# Controller.net
KiCad netlist of a schematic drawn in Altium Designer
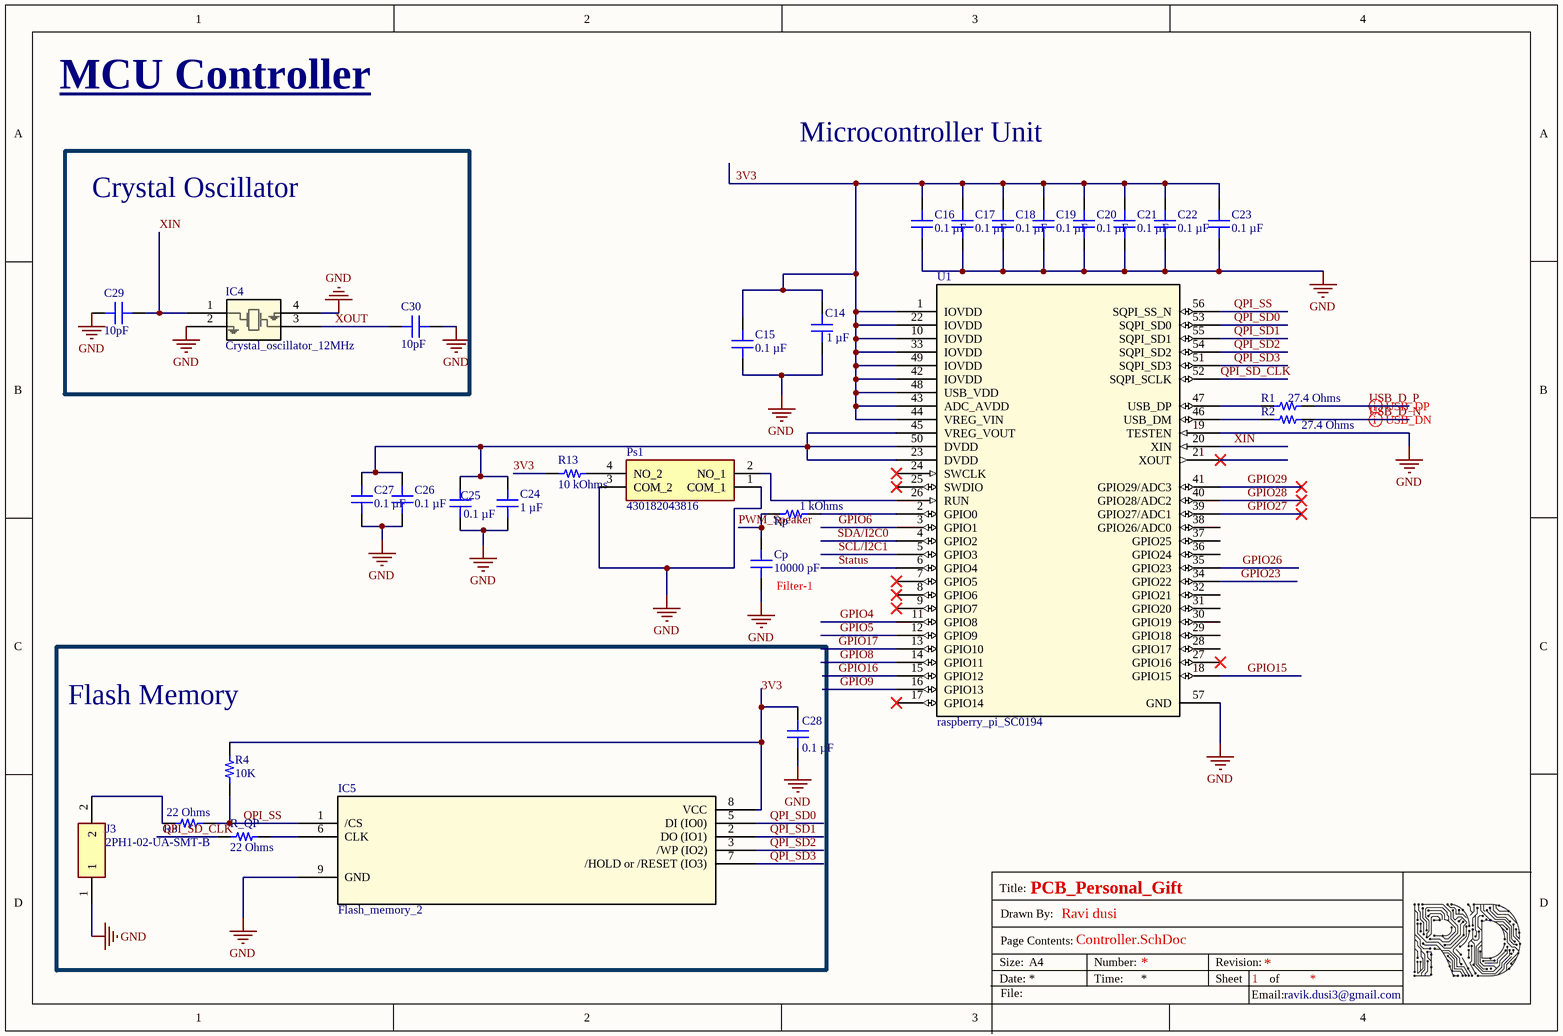
[diagram p0: Controller.SchDoc]

(export (version "E")
  (design (tool "Eeschema 10.0.6"))
  (components
    (comp (ref "C14")
      (value "1 µF")
      (footprint "CAP 0402_1005")
      (description "CAP CER 1UF 10V X7S 0402")
      (fields
        (field (name "PART NUMBER") "GRM155C71A105KE11D")
        (field (name "MANUFACTURER") "Murata Electronics")
      )
      (libsource (lib "Celestial Altium Library - altium_library") (part "Capacitor"))
    )
    (comp (ref "C15")
      (value "0.1 µF")
      (footprint "CAP 0402_1005")
      (description "CAP CER 0402 0.1UF 16V X7R 10%")
      (fields (field (name "PART NUMBER") "C0402C104K4RECAUTO") (field (name "MANUFACTURER") "KEMET"))
      (libsource (lib "Celestial Altium Library - altium_library") (part "Capacitor"))
    )
    (comp (ref "C16")
      (value "0.1 µF")
      (footprint "CAP 0402_1005")
      (description "CAP CER 0402 0.1UF 16V X7R 10%")
      (fields (field (name "PART NUMBER") "C0402C104K4RECAUTO") (field (name "MANUFACTURER") "KEMET"))
      (libsource (lib "Celestial Altium Library - altium_library") (part "Capacitor"))
    )
    (comp (ref "C17")
      (value "0.1 µF")
      (footprint "CAP 0402_1005")
      (description "CAP CER 0402 0.1UF 16V X7R 10%")
      (fields (field (name "PART NUMBER") "C0402C104K4RECAUTO") (field (name "MANUFACTURER") "KEMET"))
      (libsource (lib "Celestial Altium Library - altium_library") (part "Capacitor"))
    )
    (comp (ref "C18")
      (value "0.1 µF")
      (footprint "CAP 0402_1005")
      (description "CAP CER 0402 0.1UF 16V X7R 10%")
      (fields (field (name "PART NUMBER") "C0402C104K4RECAUTO") (field (name "MANUFACTURER") "KEMET"))
      (libsource (lib "Celestial Altium Library - altium_library") (part "Capacitor"))
    )
    (comp (ref "C19")
      (value "0.1 µF")
      (footprint "CAP 0402_1005")
      (description "CAP CER 0402 0.1UF 16V X7R 10%")
      (fields (field (name "PART NUMBER") "C0402C104K4RECAUTO") (field (name "MANUFACTURER") "KEMET"))
      (libsource (lib "Celestial Altium Library - altium_library") (part "Capacitor"))
    )
    (comp (ref "C20")
      (value "0.1 µF")
      (footprint "CAP 0402_1005")
      (description "CAP CER 0402 0.1UF 16V X7R 10%")
      (fields (field (name "PART NUMBER") "C0402C104K4RECAUTO") (field (name "MANUFACTURER") "KEMET"))
      (libsource (lib "Celestial Altium Library - altium_library") (part "Capacitor"))
    )
    (comp (ref "C21")
      (value "0.1 µF")
      (footprint "CAP 0402_1005")
      (description "CAP CER 0402 0.1UF 16V X7R 10%")
      (fields (field (name "PART NUMBER") "C0402C104K4RECAUTO") (field (name "MANUFACTURER") "KEMET"))
      (libsource (lib "Celestial Altium Library - altium_library") (part "Capacitor"))
    )
    (comp (ref "C22")
      (value "0.1 µF")
      (footprint "CAP 0402_1005")
      (description "CAP CER 0402 0.1UF 16V X7R 10%")
      (fields (field (name "PART NUMBER") "C0402C104K4RECAUTO") (field (name "MANUFACTURER") "KEMET"))
      (libsource (lib "Celestial Altium Library - altium_library") (part "Capacitor"))
    )
    (comp (ref "C23")
      (value "0.1 µF")
      (footprint "CAP 0402_1005")
      (description "CAP CER 0402 0.1UF 16V X7R 10%")
      (fields (field (name "PART NUMBER") "C0402C104K4RECAUTO") (field (name "MANUFACTURER") "KEMET"))
      (libsource (lib "Celestial Altium Library - altium_library") (part "Capacitor"))
    )
    (comp (ref "C24")
      (value "1 µF")
      (footprint "CAP 0402_1005")
      (description "CAP CER 1UF 10V X7S 0402")
      (fields
        (field (name "PART NUMBER") "GRM155C71A105KE11D")
        (field (name "MANUFACTURER") "Murata Electronics")
      )
      (libsource (lib "Celestial Altium Library - altium_library") (part "Capacitor"))
    )
    (comp (ref "C25")
      (value "0.1 µF")
      (footprint "CAP 0402_1005")
      (description "CAP CER 0402 0.1UF 16V X7R 10%")
      (fields (field (name "PART NUMBER") "C0402C104K4RECAUTO") (field (name "MANUFACTURER") "KEMET"))
      (libsource (lib "Celestial Altium Library - altium_library") (part "Capacitor"))
    )
    (comp (ref "C26")
      (value "0.1 µF")
      (footprint "CAP 0402_1005")
      (description "CAP CER 0402 0.1UF 16V X7R 10%")
      (fields (field (name "PART NUMBER") "C0402C104K4RECAUTO") (field (name "MANUFACTURER") "KEMET"))
      (libsource (lib "Celestial Altium Library - altium_library") (part "Capacitor"))
    )
    (comp (ref "C27")
      (value "0.1 µF")
      (footprint "CAP 0402_1005")
      (description "CAP CER 0402 0.1UF 16V X7R 10%")
      (fields (field (name "PART NUMBER") "C0402C104K4RECAUTO") (field (name "MANUFACTURER") "KEMET"))
      (libsource (lib "Celestial Altium Library - altium_library") (part "Capacitor"))
    )
    (comp (ref "C28")
      (value "0.1 µF")
      (footprint "CAP 0402_1005")
      (description "CAP CER 0402 0.1UF 16V X7R 10%")
      (fields (field (name "PART NUMBER") "C0402C104K4RECAUTO") (field (name "MANUFACTURER") "KEMET"))
      (libsource (lib "Celestial Altium Library - altium_library") (part "Capacitor"))
    )
    (comp (ref "C29")
      (value "10pF")
      (footprint "CAP 0402_1005")
      (description "CAP CER 10PF 50V C0G/NP0 0402")
      (fields (field (name "PART NUMBER") "04025U100JAT2A") (field (name "MANUFACTURER") "AVX Corporation"))
      (libsource (lib "Celestial Altium Library - altium_library") (part "Capacitor"))
    )
    (comp (ref "C30")
      (value "10pF")
      (footprint "CAP 0402_1005")
      (description "CAP CER 10PF 50V C0G/NP0 0402")
      (fields (field (name "PART NUMBER") "04025U100JAT2A") (field (name "MANUFACTURER") "AVX Corporation"))
      (libsource (lib "Celestial Altium Library - altium_library") (part "Capacitor"))
    )
    (comp (ref "Cp")
      (value "10000 pF")
      (footprint "CAP 0402_1005")
      (description "CAP CER 0402 10NF 50V X7R 20%")
      (fields
        (field (name "PART NUMBER") "C0402C103M5RECAUTO")
        (field (name "CAPACITANCE") "10000 pF")
        (field (name "MANUFACTURER") "KEMET")
      )
      (libsource (lib "Celestial Altium Library - altium_library (1)") (part "Capacitor"))
    )
    (comp (ref "IC4")
      (value "Crystal_oscillator_12MHz")
      (footprint "ABM8-272-T3_ABR")
      (libsource (lib "Personal_proj_lib") (part "Crystal_oscillator_12MHz"))
    )
    (comp (ref "IC5")
      (value "Flash_memory_2")
      (footprint "SON127P610X510X80-8N430X340")
      (description "FLASH - NOR Memory IC 128Mb (16M x 8) SPI - Quad I/O, QPI, DTR 133 MHz 8-SOIC")
      (libsource (lib "Personal_proj_lib") (part "Flash_memory_2"))
    )
    (comp (ref "J3")
      (value "2PH1-02-UA-SMT-B")
      (footprint "SamacSys:2PH102UASMTB")
      (description "Connector")
      (fields (field (name "MOUSER PART NUMBER") "737-2PH1-02-UA-SMT-B"))
      (libsource (lib "*") (part "2PH1-02-UA-SMT-B"))
    )
    (comp (ref "Ps1")
      (value "430182043816")
      (footprint "SamacSys:430182043816")
      (description "Switch")
      (fields (field (name "MOUSER PART NUMBER") "710-430182043816"))
      (libsource (lib "*") (part "430182043816"))
    )
    (comp (ref "R1")
      (value "27.4 Ohms")
      (footprint "RES 0402_1005")
      (description "RES 27.4 OHM 1% 1/16W 0402")
      (fields (field (name "PART NUMBER") "RC0402FR-0727R4L") (field (name "MANUFACTURER") "Yageo"))
      (libsource (lib "Celestial Altium Library - altium_library") (part "Resistor"))
    )
    (comp (ref "R2")
      (value "27.4 Ohms")
      (footprint "RES 0402_1005")
      (description "RES 27.4 OHM 1% 1/16W 0402")
      (fields (field (name "PART NUMBER") "RC0402FR-0727R4L") (field (name "MANUFACTURER") "Yageo"))
      (libsource (lib "Celestial Altium Library - altium_library") (part "Resistor"))
    )
    (comp (ref "R3")
      (value "22 Ohms")
      (footprint "RES 0402_1005")
      (description "RES SMD 22 OHM 0.5% 1/16W 0402")
      (fields (field (name "PART NUMBER") "RR0510R-220-D") (field (name "MANUFACTURER") "Susumu"))
      (libsource (lib "Celestial Altium Library - altium_library (1)") (part "Resistor"))
    )
    (comp (ref "R4")
      (value "10K")
      (footprint "RES 0402_1005")
      (description "RES 10K OHM 0.1% 1/10W 0402")
      (fields
        (field (name "PART NUMBER") "RP73PF1E10KBTD")
        (field (name "MANUFACTURER") "TE Connectivity Passive Product")
      )
      (libsource (lib "Celestial Altium Library - altium_library") (part "Resistor"))
    )
    (comp (ref "R13")
      (value "10 kOhms")
      (footprint "RES 0402_1005")
      (description "RES 10K OHM 0.1% 1/10W 0402")
      (fields
        (field (name "PART NUMBER") "RP73PF1E10KBTD")
        (field (name "MANUFACTURER") "TE Connectivity Passive Product")
      )
      (libsource (lib "Celestial Altium Library - altium_library") (part "Resistor"))
    )
    (comp (ref "Rp")
      (value "1 kOhms")
      (footprint "YAGEO RES 0402_1005")
      (description "RES SMD 1K OHM 0.1% 1/16W 0402")
      (fields (field (name "PART NUMBER") "AT0402BRD071KL") (field (name "MANUFACTURER") "Yageo"))
      (libsource (lib "Celestial Altium Library - altium_library (1)") (part "Resistor"))
    )
    (comp (ref "R_QP")
      (value "22 Ohms")
      (footprint "RES 0402_1005")
      (description "RES SMD 22 OHM 0.5% 1/16W 0402")
      (fields (field (name "PART NUMBER") "RR0510R-220-D") (field (name "MANUFACTURER") "Susumu"))
      (libsource (lib "Celestial Altium Library - altium_library (1)") (part "Resistor"))
    )
    (comp (ref "U1")
      (value "raspberry_pi_SC0194")
      (footprint "QFN56_7X7_RPI")
      (description "rp2040 rapberri Pi Microcontroller")
      (libsource (lib "Personal_proj_lib") (part "raspberry_pi_SC0194"))
    )
  )
  (nets
    (net (code "1") (name "/3V3") (class "Default")
      (node (ref "C14") (pin "2") (pinfunction "2_2") (pintype "passive"))
      (node (ref "C15") (pin "2") (pinfunction "2_2") (pintype "passive"))
      (node (ref "C16") (pin "2") (pinfunction "2_2") (pintype "passive"))
      (node (ref "C17") (pin "2") (pinfunction "2_2") (pintype "passive"))
      (node (ref "C18") (pin "2") (pinfunction "2_2") (pintype "passive"))
      (node (ref "C19") (pin "2") (pinfunction "2_2") (pintype "passive"))
      (node (ref "C20") (pin "2") (pinfunction "2_2") (pintype "passive"))
      (node (ref "C21") (pin "2") (pinfunction "2_2") (pintype "passive"))
      (node (ref "C22") (pin "2") (pinfunction "2_2") (pintype "passive"))
      (node (ref "C23") (pin "2") (pinfunction "2_2") (pintype "passive"))
      (node (ref "C28") (pin "2") (pinfunction "2_2") (pintype "passive"))
      (node (ref "IC5") (pin "8") (pinfunction "VCC_8") (pintype "power_in"))
      (node (ref "R13") (pin "1") (pinfunction "1_1") (pintype "passive"))
      (node (ref "R4") (pin "2") (pinfunction "2_2") (pintype "passive"))
      (node (ref "U1") (pin "1") (pinfunction "IOVDD_1") (pintype "power_in"))
      (node (ref "U1") (pin "10") (pinfunction "IOVDD_10") (pintype "power_in"))
      (node (ref "U1") (pin "22") (pinfunction "IOVDD_22") (pintype "power_in"))
      (node (ref "U1") (pin "33") (pinfunction "IOVDD_33") (pintype "power_in"))
      (node (ref "U1") (pin "42") (pinfunction "IOVDD_42") (pintype "power_in"))
      (node (ref "U1") (pin "43") (pinfunction "ADC_AVDD_43") (pintype "power_in"))
      (node (ref "U1") (pin "44") (pinfunction "VREG_VIN_44") (pintype "power_in"))
      (node (ref "U1") (pin "48") (pinfunction "USB_VDD_48") (pintype "power_in"))
      (node (ref "U1") (pin "49") (pinfunction "IOVDD_49") (pintype "power_in"))
    )
    (net (code "2") (name "/GPIO4") (class "Default")
      (node (ref "U1") (pin "11") (pinfunction "GPIO8_11") (pintype "bidirectional"))
    )
    (net (code "3") (name "/GPIO5") (class "Default")
      (node (ref "U1") (pin "12") (pinfunction "GPIO9_12") (pintype "bidirectional"))
    )
    (net (code "4") (name "/GPIO6") (class "Default")
      (node (ref "U1") (pin "3") (pinfunction "GPIO1_3") (pintype "bidirectional"))
    )
    (net (code "5") (name "/GPIO8") (class "Default")
      (node (ref "U1") (pin "14") (pinfunction "GPIO11_14") (pintype "bidirectional"))
    )
    (net (code "6") (name "/GPIO9") (class "Default")
      (node (ref "U1") (pin "16") (pinfunction "GPIO13_16") (pintype "bidirectional"))
    )
    (net (code "7") (name "/GPIO15") (class "Default")
      (node (ref "U1") (pin "18") (pinfunction "GPIO15_18") (pintype "bidirectional"))
    )
    (net (code "8") (name "/GPIO16") (class "Default")
      (node (ref "U1") (pin "15") (pinfunction "GPIO12_15") (pintype "bidirectional"))
    )
    (net (code "9") (name "/GPIO17") (class "Default")
      (node (ref "U1") (pin "13") (pinfunction "GPIO10_13") (pintype "bidirectional"))
    )
    (net (code "10") (name "/GPIO23") (class "Default")
      (node (ref "U1") (pin "34") (pinfunction "GPIO22_34") (pintype "bidirectional"))
    )
    (net (code "11") (name "/GPIO26") (class "Default")
      (node (ref "U1") (pin "35") (pinfunction "GPIO23_35") (pintype "bidirectional"))
    )
    (net (code "12") (name "/GPIO27") (class "Default")
      (node (ref "U1") (pin "39") (pinfunction "GPIO27/ADC1_39") (pintype "bidirectional+no_connect"))
    )
    (net (code "13") (name "/GPIO28") (class "Default")
      (node (ref "U1") (pin "40") (pinfunction "GPIO28/ADC2_40") (pintype "bidirectional+no_connect"))
    )
    (net (code "14") (name "/GPIO29") (class "Default")
      (node (ref "U1") (pin "41") (pinfunction "GPIO29/ADC3_41") (pintype "bidirectional+no_connect"))
    )
    (net (code "15") (name "/PWM_Speaker") (class "Default")
      (node (ref "Cp") (pin "2") (pinfunction "2_2") (pintype "passive"))
      (node (ref "Rp") (pin "1") (pinfunction "1_1") (pintype "passive"))
    )
    (net (code "16") (name "/QPI_SD0") (class "Default")
      (node (ref "IC5") (pin "5") (pinfunction "DI_(IO0)_5") (pintype "passive"))
      (node (ref "U1") (pin "53") (pinfunction "SQPI_SD0_53") (pintype "bidirectional"))
    )
    (net (code "17") (name "/QPI_SD1") (class "Default")
      (node (ref "IC5") (pin "2") (pinfunction "DO_(IO1)_2") (pintype "passive"))
      (node (ref "U1") (pin "55") (pinfunction "SQPI_SD1_55") (pintype "bidirectional"))
    )
    (net (code "18") (name "/QPI_SD2") (class "Default")
      (node (ref "IC5") (pin "3") (pinfunction "/WP_(IO2)_3") (pintype "passive"))
      (node (ref "U1") (pin "54") (pinfunction "SQPI_SD2_54") (pintype "bidirectional"))
    )
    (net (code "19") (name "/QPI_SD3") (class "Default")
      (node (ref "IC5") (pin "7") (pinfunction "/HOLD_or_/RESET_(IO3)_7") (pintype "passive"))
      (node (ref "U1") (pin "51") (pinfunction "SQPI_SD3_51") (pintype "bidirectional"))
    )
    (net (code "20") (name "/QPI_SD_CLK") (class "Default")
      (node (ref "R_QP") (pin "1") (pinfunction "1_1") (pintype "passive"))
      (node (ref "U1") (pin "52") (pinfunction "SQPI_SCLK_52") (pintype "bidirectional"))
    )
    (net (code "21") (name "/QPI_SS") (class "Default")
      (node (ref "IC5") (pin "1") (pinfunction "/CS_1") (pintype "passive"))
      (node (ref "R3") (pin "2") (pinfunction "2_2") (pintype "passive"))
      (node (ref "R4") (pin "1") (pinfunction "1_1") (pintype "passive"))
      (node (ref "U1") (pin "56") (pinfunction "SQPI_SS_N_56") (pintype "bidirectional"))
    )
    (net (code "22") (name "/SCL{slash}I2C1") (class "Default")
      (node (ref "U1") (pin "5") (pinfunction "GPIO3_5") (pintype "bidirectional"))
    )
    (net (code "23") (name "/SDA{slash}I2C0") (class "Default")
      (node (ref "U1") (pin "4") (pinfunction "GPIO2_4") (pintype "bidirectional"))
    )
    (net (code "24") (name "/Status") (class "Default")
      (node (ref "U1") (pin "6") (pinfunction "GPIO4_6") (pintype "bidirectional"))
    )
    (net (code "25") (name "/USB_D_N") (class "Default")
      (node (ref "R2") (pin "2") (pinfunction "2_2") (pintype "passive"))
    )
    (net (code "26") (name "/USB_D_P") (class "Default")
      (node (ref "R1") (pin "2") (pinfunction "2_2") (pintype "passive"))
    )
    (net (code "27") (name "/XIN") (class "Default")
      (node (ref "C29") (pin "2") (pinfunction "2_2") (pintype "passive"))
      (node (ref "IC4") (pin "1") (pinfunction "1_1") (pintype "passive"))
      (node (ref "U1") (pin "20") (pinfunction "XIN_20") (pintype "input"))
    )
    (net (code "28") (name "/XOUT") (class "Default")
      (node (ref "C30") (pin "1") (pinfunction "1_1") (pintype "passive"))
      (node (ref "IC4") (pin "3") (pinfunction "3_3") (pintype "passive"))
    )
    (net (code "29") (name "GND") (class "Default")
      (node (ref "C14") (pin "1") (pinfunction "1_1") (pintype "passive"))
      (node (ref "C15") (pin "1") (pinfunction "1_1") (pintype "passive"))
      (node (ref "C16") (pin "1") (pinfunction "1_1") (pintype "passive"))
      (node (ref "C17") (pin "1") (pinfunction "1_1") (pintype "passive"))
      (node (ref "C18") (pin "1") (pinfunction "1_1") (pintype "passive"))
      (node (ref "C19") (pin "1") (pinfunction "1_1") (pintype "passive"))
      (node (ref "C20") (pin "1") (pinfunction "1_1") (pintype "passive"))
      (node (ref "C21") (pin "1") (pinfunction "1_1") (pintype "passive"))
      (node (ref "C22") (pin "1") (pinfunction "1_1") (pintype "passive"))
      (node (ref "C23") (pin "1") (pinfunction "1_1") (pintype "passive"))
      (node (ref "C24") (pin "1") (pinfunction "1_1") (pintype "passive"))
      (node (ref "C25") (pin "1") (pinfunction "1_1") (pintype "passive"))
      (node (ref "C26") (pin "1") (pinfunction "1_1") (pintype "passive"))
      (node (ref "C27") (pin "1") (pinfunction "1_1") (pintype "passive"))
      (node (ref "C28") (pin "1") (pinfunction "1_1") (pintype "passive"))
      (node (ref "C29") (pin "1") (pinfunction "1_1") (pintype "passive"))
      (node (ref "C30") (pin "2") (pinfunction "2_2") (pintype "passive"))
      (node (ref "Cp") (pin "1") (pinfunction "1_1") (pintype "passive"))
      (node (ref "IC4") (pin "2") (pinfunction "2_2") (pintype "passive"))
      (node (ref "IC4") (pin "4") (pinfunction "4_4") (pintype "passive"))
      (node (ref "IC5") (pin "9") (pinfunction "GND_9") (pintype "passive"))
      (node (ref "J3") (pin "1") (pinfunction "1_1") (pintype "passive"))
      (node (ref "Ps1") (pin "1") (pinfunction "COM_1_1") (pintype "passive"))
      (node (ref "Ps1") (pin "3") (pinfunction "COM_2_3") (pintype "passive"))
      (node (ref "U1") (pin "19") (pinfunction "TESTEN_19") (pintype "input"))
      (node (ref "U1") (pin "57") (pinfunction "GND_57") (pintype "power_in"))
    )
    (net (code "30") (name "Net-(IC5-CLK)") (class "Default")
      (node (ref "IC5") (pin "6") (pinfunction "CLK_6") (pintype "passive"))
      (node (ref "R_QP") (pin "2") (pinfunction "2_2") (pintype "passive"))
    )
    (net (code "31") (name "Net-(J3-Pad2)") (class "Default")
      (node (ref "J3") (pin "2") (pinfunction "2_2") (pintype "passive"))
      (node (ref "R3") (pin "1") (pinfunction "1_1") (pintype "passive"))
    )
    (net (code "32") (name "Net-(Ps1-NO_1)") (class "Default")
      (node (ref "Ps1") (pin "2") (pinfunction "NO_1_2") (pintype "passive"))
      (node (ref "U1") (pin "26") (pinfunction "RUN_26") (pintype "input"))
    )
    (net (code "33") (name "Net-(Ps1-NO_2)") (class "Default")
      (node (ref "Ps1") (pin "4") (pinfunction "NO_2_4") (pintype "passive"))
      (node (ref "R13") (pin "2") (pinfunction "2_2") (pintype "passive"))
    )
    (net (code "34") (name "Net-(U1-GPIO0)") (class "Default")
      (node (ref "Rp") (pin "2") (pinfunction "2_2") (pintype "passive"))
      (node (ref "U1") (pin "2") (pinfunction "GPIO0_2") (pintype "bidirectional"))
    )
    (net (code "35") (name "Net-(U1-USB_DM)") (class "Default")
      (node (ref "R2") (pin "1") (pinfunction "1_1") (pintype "passive"))
      (node (ref "U1") (pin "46") (pinfunction "USB_DM_46") (pintype "bidirectional"))
    )
    (net (code "36") (name "Net-(U1-USB_DP)") (class "Default")
      (node (ref "R1") (pin "1") (pinfunction "1_1") (pintype "passive"))
      (node (ref "U1") (pin "47") (pinfunction "USB_DP_47") (pintype "bidirectional"))
    )
    (net (code "37") (name "Net-(U1-VREG_VOUT)") (class "Default")
      (node (ref "C24") (pin "2") (pinfunction "2_2") (pintype "passive"))
      (node (ref "C25") (pin "2") (pinfunction "2_2") (pintype "passive"))
      (node (ref "C26") (pin "2") (pinfunction "2_2") (pintype "passive"))
      (node (ref "C27") (pin "2") (pinfunction "2_2") (pintype "passive"))
      (node (ref "U1") (pin "23") (pinfunction "DVDD_23") (pintype "power_in"))
      (node (ref "U1") (pin "45") (pinfunction "VREG_VOUT_45") (pintype "power_in"))
      (node (ref "U1") (pin "50") (pinfunction "DVDD_50") (pintype "power_in"))
    )
    (net (code "38") (name "unconnected-(U1-GPIO5-Pad7)") (class "Default")
      (node (ref "U1") (pin "7") (pinfunction "GPIO5_7") (pintype "bidirectional+no_connect"))
    )
    (net (code "39") (name "unconnected-(U1-GPIO6-Pad8)") (class "Default")
      (node (ref "U1") (pin "8") (pinfunction "GPIO6_8") (pintype "bidirectional+no_connect"))
    )
    (net (code "40") (name "unconnected-(U1-GPIO7-Pad9)") (class "Default")
      (node (ref "U1") (pin "9") (pinfunction "GPIO7_9") (pintype "bidirectional+no_connect"))
    )
    (net (code "41") (name "unconnected-(U1-GPIO14-Pad17)") (class "Default")
      (node (ref "U1") (pin "17") (pinfunction "GPIO14_17") (pintype "bidirectional+no_connect"))
    )
    (net (code "42") (name "unconnected-(U1-GPIO16-Pad27)") (class "Default")
      (node (ref "U1") (pin "27") (pinfunction "GPIO16_27") (pintype "bidirectional+no_connect"))
    )
    (net (code "43") (name "unconnected-(U1-GPIO17-Pad28)") (class "Default")
      (node (ref "U1") (pin "28") (pinfunction "GPIO17_28") (pintype "bidirectional"))
    )
    (net (code "44") (name "unconnected-(U1-GPIO18-Pad29)") (class "Default")
      (node (ref "U1") (pin "29") (pinfunction "GPIO18_29") (pintype "bidirectional"))
    )
    (net (code "45") (name "unconnected-(U1-GPIO19-Pad30)") (class "Default")
      (node (ref "U1") (pin "30") (pinfunction "GPIO19_30") (pintype "bidirectional"))
    )
    (net (code "46") (name "unconnected-(U1-GPIO20-Pad31)") (class "Default")
      (node (ref "U1") (pin "31") (pinfunction "GPIO20_31") (pintype "bidirectional"))
    )
    (net (code "47") (name "unconnected-(U1-GPIO21-Pad32)") (class "Default")
      (node (ref "U1") (pin "32") (pinfunction "GPIO21_32") (pintype "bidirectional"))
    )
    (net (code "48") (name "unconnected-(U1-GPIO24-Pad36)") (class "Default")
      (node (ref "U1") (pin "36") (pinfunction "GPIO24_36") (pintype "bidirectional"))
    )
    (net (code "49") (name "unconnected-(U1-GPIO25-Pad37)") (class "Default")
      (node (ref "U1") (pin "37") (pinfunction "GPIO25_37") (pintype "bidirectional"))
    )
    (net (code "50") (name "unconnected-(U1-GPIO26{slash}ADC0-Pad38)") (class "Default")
      (node (ref "U1") (pin "38") (pinfunction "GPIO26/ADC0_38") (pintype "bidirectional"))
    )
    (net (code "51") (name "unconnected-(U1-SWCLK-Pad24)") (class "Default")
      (node (ref "U1") (pin "24") (pinfunction "SWCLK_24") (pintype "input+no_connect"))
    )
    (net (code "52") (name "unconnected-(U1-SWDIO-Pad25)") (class "Default")
      (node (ref "U1") (pin "25") (pinfunction "SWDIO_25") (pintype "bidirectional+no_connect"))
    )
    (net (code "53") (name "unconnected-(U1-XOUT-Pad21)") (class "Default")
      (node (ref "U1") (pin "21") (pinfunction "XOUT_21") (pintype "output+no_connect"))
    )
  )
)
